# Connectors.net
KiCad netlist of a schematic drawn in Altium Designer
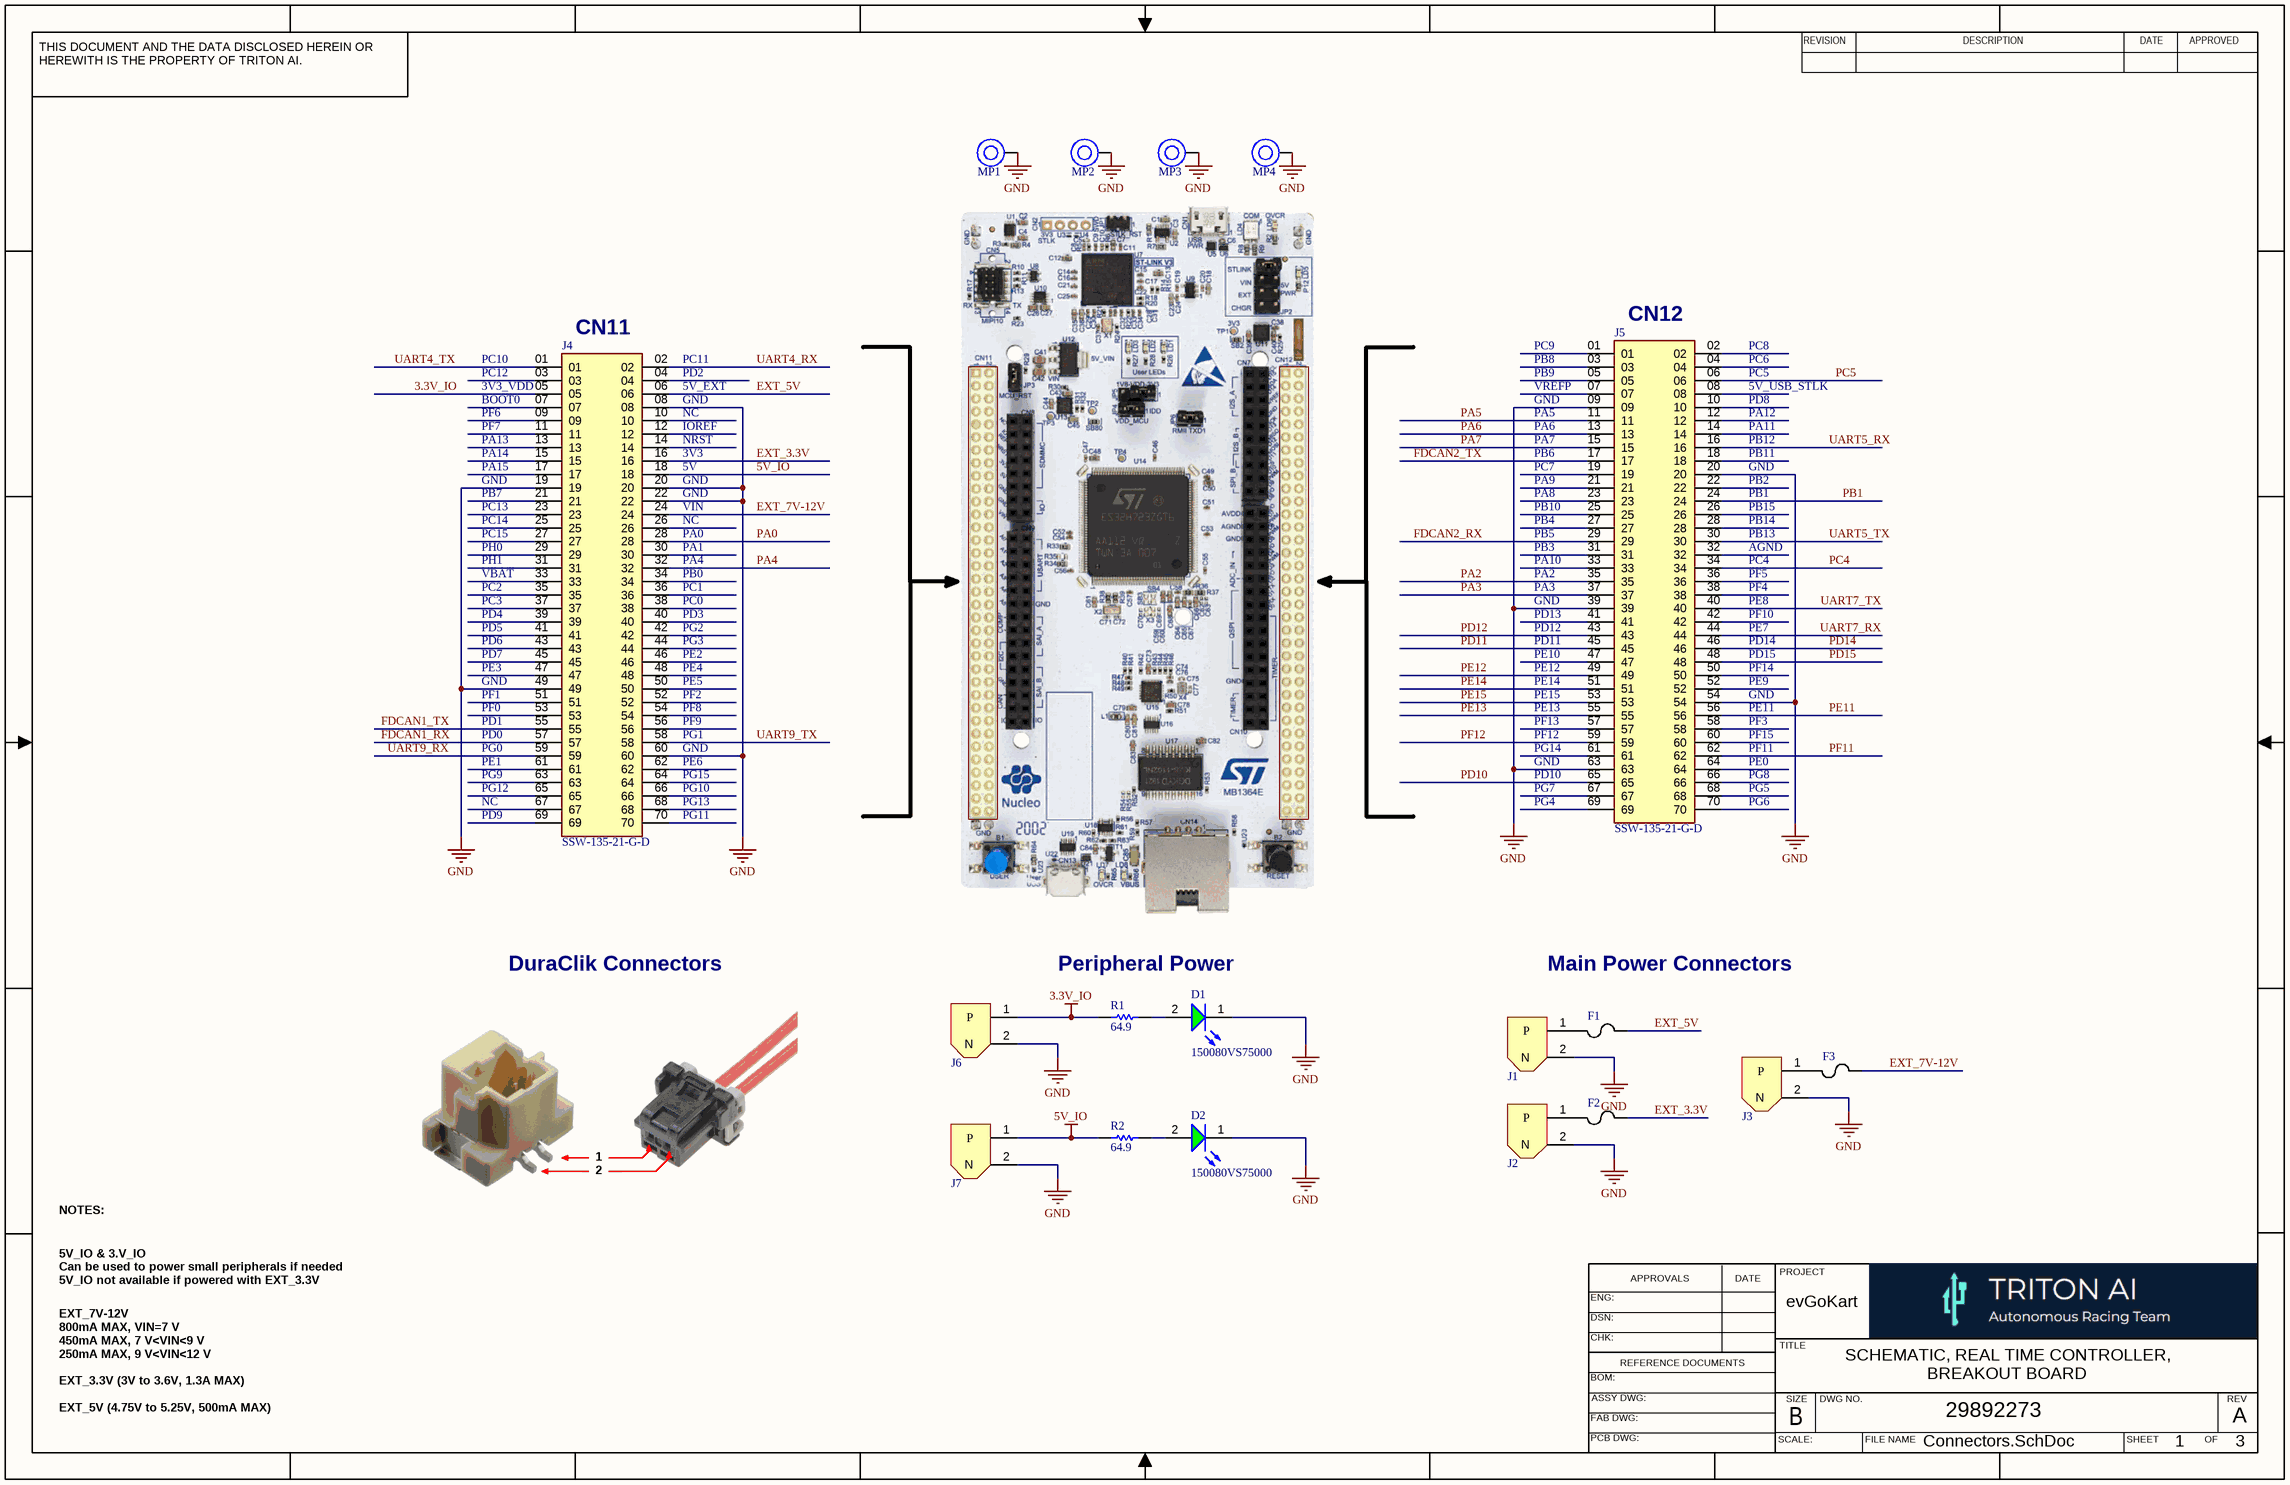
[diagram p0: Connectors.SchDoc]

(export (version "E")
  (design (tool "Eeschema 10.0.6"))
  (components
    (comp (ref "D1")
      (value "150080VS75000")
      (footprint "WL-SMCW_0805_150080xx75000")
      (description "WL-SMCW SMT Mono-Color Chip LED Waterclear")
      (libsource (lib "Altium Content Vault") (part "LED_Green_2A-1K"))
    )
    (comp (ref "D2")
      (value "150080VS75000")
      (footprint "WL-SMCW_0805_150080xx75000")
      (description "WL-SMCW SMT Mono-Color Chip LED Waterclear")
      (libsource (lib "Altium Content Vault") (part "LED_Green_2A-1K"))
    )
    (comp (ref "F1")
      (value "500mA")
      (footprint "FUS_VISHAY_MFU0805_VIS")
      (description "MFU0805FF00500P500")
      (libsource (lib "MFU0805FF00500P500") (part "MFU0805FF00500P500"))
    )
    (comp (ref "F2")
      (value "1.5A")
      (footprint "FUS_VISHAY_MFU0805_VIS")
      (description "MFU0805FF01500P100")
      (libsource (lib "MFU0805FF01500P100") (part "MFU0805FF01500P100"))
    )
    (comp (ref "F3")
      (value "800mA")
      (footprint "FUS_VISHAY_MFU0805_VIS")
      (description "MFU0805FF00800P100")
      (libsource (lib "MFU0805FF00800P100") (part "MFU0805FF00800P100"))
    )
    (comp (ref "J1")
      (value "XT30UPB-M")
      (footprint "XT30UPB-M")
      (description "Socket; DC supply; XT30; male; PIN: 2; on PCBs; THT; yellow; 15A; 500V")
      (fields (field (name "MF") "amass"))
      (libsource (lib "XT30UPB-M") (part "XT30UPB-M"))
    )
    (comp (ref "J2")
      (value "XT30UPB-M")
      (footprint "XT30UPB-M")
      (description "Socket; DC supply; XT30; male; PIN: 2; on PCBs; THT; yellow; 15A; 500V")
      (fields (field (name "MF") "amass"))
      (libsource (lib "XT30UPB-M") (part "XT30UPB-M"))
    )
    (comp (ref "J3")
      (value "XT30UPB-M")
      (footprint "XT30UPB-M")
      (description "Socket; DC supply; XT30; male; PIN: 2; on PCBs; THT; yellow; 15A; 500V")
      (fields (field (name "MF") "amass"))
      (libsource (lib "XT30UPB-M") (part "XT30UPB-M"))
    )
    (comp (ref "J4")
      (value "SSW-135-21-G-D")
      (footprint "SAMTEC_SSW-135-21-G-D")
      (fields (field (name "MF") "{'manufacturer': u'Samtec Inc.'}"))
      (libsource (lib "SSW-135-21-G-D") (part "SSW-135-21-G-D"))
    )
    (comp (ref "J5")
      (value "SSW-135-21-G-D")
      (footprint "SAMTEC_SSW-135-21-G-D")
      (fields (field (name "MF") "{'manufacturer': u'Samtec Inc.'}"))
      (libsource (lib "SSW-135-21-G-D") (part "SSW-135-21-G-D"))
    )
    (comp (ref "J6")
      (value "XT30UPB-M")
      (footprint "XT30UPB-M")
      (description "Socket; DC supply; XT30; male; PIN: 2; on PCBs; THT; yellow; 15A; 500V")
      (fields (field (name "MF") "amass"))
      (libsource (lib "XT30UPB-M") (part "XT30UPB-M"))
    )
    (comp (ref "J7")
      (value "XT30UPB-M")
      (footprint "XT30UPB-M")
      (description "Socket; DC supply; XT30; male; PIN: 2; on PCBs; THT; yellow; 15A; 500V")
      (fields (field (name "MF") "amass"))
      (libsource (lib "XT30UPB-M") (part "XT30UPB-M"))
    )
    (comp (ref "MP1")
      (value "M2.5 x 9mm")
      (footprint "9774090151")
      (description "WA-SMSI SMT Steel Spacer with internal Thread, OD 5.1mm, M2.5 x 9mm")
      (fields
        (field (name "MANUFACTURER PART NUMBER") "9774090151R")
        (field (name "MANUFACTURER") "Wurth Elektronik")
      )
      (libsource (lib "Altium_WA-SMSI_rev22a") (part "9774090151R"))
    )
    (comp (ref "MP2")
      (value "M2.5 x 9mm")
      (footprint "9774090151")
      (description "WA-SMSI SMT Steel Spacer with internal Thread, OD 5.1mm, M2.5 x 9mm")
      (fields
        (field (name "MANUFACTURER PART NUMBER") "9774090151R")
        (field (name "MANUFACTURER") "Wurth Elektronik")
      )
      (libsource (lib "Altium_WA-SMSI_rev22a") (part "9774090151R"))
    )
    (comp (ref "MP3")
      (value "M2.5 x 9mm")
      (footprint "9774090151")
      (description "WA-SMSI SMT Steel Spacer with internal Thread, OD 5.1mm, M2.5 x 9mm")
      (fields
        (field (name "MANUFACTURER PART NUMBER") "9774090151R")
        (field (name "MANUFACTURER") "Wurth Elektronik")
      )
      (libsource (lib "Altium_WA-SMSI_rev22a") (part "9774090151R"))
    )
    (comp (ref "MP4")
      (value "M2.5 x 9mm")
      (footprint "9774090151")
      (description "WA-SMSI SMT Steel Spacer with internal Thread, OD 5.1mm, M2.5 x 9mm")
      (fields
        (field (name "MANUFACTURER PART NUMBER") "9774090151R")
        (field (name "MANUFACTURER") "Wurth Elektronik")
      )
      (libsource (lib "Altium_WA-SMSI_rev22a") (part "9774090151R"))
    )
    (comp (ref "R1")
      (value "64.9")
      (footprint "RESC2013X60X35LL10T20")
      (fields (field (name "PART NUMBER") "RC0805FR-0764R9L") (field (name "MANUFACTURER") "Yageo"))
      (libsource (lib "Altium Content Vault") (part "RES"))
    )
    (comp (ref "R2")
      (value "64.9")
      (footprint "RESC2013X60X35LL10T20")
      (fields (field (name "PART NUMBER") "RC0805FR-0764R9L") (field (name "MANUFACTURER") "Yageo"))
      (libsource (lib "Altium Content Vault") (part "RES"))
    )
  )
  (nets
    (net (code "1") (name "/EXT_3.3V") (class "Default")
      (node (ref "F2") (pin "1") (pinfunction "1_1") (pintype "passive"))
      (node (ref "J4") (pin "16") (pinfunction "16_16") (pintype "passive"))
    )
    (net (code "2") (name "/EXT_5V") (class "Default")
      (node (ref "F1") (pin "1") (pinfunction "1_1") (pintype "passive"))
      (node (ref "J4") (pin "06") (pinfunction "06_06") (pintype "passive"))
    )
    (net (code "3") (name "/EXT_7V-12V") (class "Default")
      (node (ref "F3") (pin "1") (pinfunction "1_1") (pintype "passive"))
      (node (ref "J4") (pin "24") (pinfunction "24_24") (pintype "passive"))
    )
    (net (code "4") (name "/FDCAN1_RX") (class "Default")
      (node (ref "J4") (pin "57") (pinfunction "57_57") (pintype "passive"))
    )
    (net (code "5") (name "/FDCAN1_TX") (class "Default")
      (node (ref "J4") (pin "55") (pinfunction "55_55") (pintype "passive"))
    )
    (net (code "6") (name "/FDCAN2_RX") (class "Default")
      (node (ref "J5") (pin "29") (pinfunction "29_29") (pintype "passive"))
    )
    (net (code "7") (name "/FDCAN2_TX") (class "Default")
      (node (ref "J5") (pin "17") (pinfunction "17_17") (pintype "passive"))
    )
    (net (code "8") (name "/PA0") (class "Default")
      (node (ref "J4") (pin "28") (pinfunction "28_28") (pintype "passive"))
    )
    (net (code "9") (name "/PA2") (class "Default")
      (node (ref "J5") (pin "35") (pinfunction "35_35") (pintype "passive"))
    )
    (net (code "10") (name "/PA3") (class "Default")
      (node (ref "J5") (pin "37") (pinfunction "37_37") (pintype "passive"))
    )
    (net (code "11") (name "/PA4") (class "Default")
      (node (ref "J4") (pin "32") (pinfunction "32_32") (pintype "passive"))
    )
    (net (code "12") (name "/PA5") (class "Default")
      (node (ref "J5") (pin "11") (pinfunction "11_11") (pintype "passive"))
    )
    (net (code "13") (name "/PA6") (class "Default")
      (node (ref "J5") (pin "13") (pinfunction "13_13") (pintype "passive"))
    )
    (net (code "14") (name "/PA7") (class "Default")
      (node (ref "J5") (pin "15") (pinfunction "15_15") (pintype "passive"))
    )
    (net (code "15") (name "/PB1") (class "Default")
      (node (ref "J5") (pin "24") (pinfunction "24_24") (pintype "passive"))
    )
    (net (code "16") (name "/PC4") (class "Default")
      (node (ref "J5") (pin "34") (pinfunction "34_34") (pintype "passive"))
    )
    (net (code "17") (name "/PC5") (class "Default")
      (node (ref "J5") (pin "06") (pinfunction "06_06") (pintype "passive"))
    )
    (net (code "18") (name "/PD10") (class "Default")
      (node (ref "J5") (pin "65") (pinfunction "65_65") (pintype "passive"))
    )
    (net (code "19") (name "/PD11") (class "Default")
      (node (ref "J5") (pin "45") (pinfunction "45_45") (pintype "passive"))
    )
    (net (code "20") (name "/PD12") (class "Default")
      (node (ref "J5") (pin "43") (pinfunction "43_43") (pintype "passive"))
    )
    (net (code "21") (name "/PD14") (class "Default")
      (node (ref "J5") (pin "46") (pinfunction "46_46") (pintype "passive"))
    )
    (net (code "22") (name "/PD15") (class "Default")
      (node (ref "J5") (pin "48") (pinfunction "48_48") (pintype "passive"))
    )
    (net (code "23") (name "/PE11") (class "Default")
      (node (ref "J5") (pin "56") (pinfunction "56_56") (pintype "passive"))
    )
    (net (code "24") (name "/PE12") (class "Default")
      (node (ref "J5") (pin "49") (pinfunction "49_49") (pintype "passive"))
    )
    (net (code "25") (name "/PE13") (class "Default")
      (node (ref "J5") (pin "55") (pinfunction "55_55") (pintype "passive"))
    )
    (net (code "26") (name "/PE14") (class "Default")
      (node (ref "J5") (pin "51") (pinfunction "51_51") (pintype "passive"))
    )
    (net (code "27") (name "/PE15") (class "Default")
      (node (ref "J5") (pin "53") (pinfunction "53_53") (pintype "passive"))
    )
    (net (code "28") (name "/PF11") (class "Default")
      (node (ref "J5") (pin "62") (pinfunction "62_62") (pintype "passive"))
    )
    (net (code "29") (name "/PF12") (class "Default")
      (node (ref "J5") (pin "59") (pinfunction "59_59") (pintype "passive"))
    )
    (net (code "30") (name "/UART4_RX") (class "Default")
      (node (ref "J4") (pin "02") (pinfunction "02_02") (pintype "passive"))
    )
    (net (code "31") (name "/UART4_TX") (class "Default")
      (node (ref "J4") (pin "01") (pinfunction "01_01") (pintype "passive"))
    )
    (net (code "32") (name "/UART5_RX") (class "Default")
      (node (ref "J5") (pin "16") (pinfunction "16_16") (pintype "passive"))
    )
    (net (code "33") (name "/UART5_TX") (class "Default")
      (node (ref "J5") (pin "30") (pinfunction "30_30") (pintype "passive"))
    )
    (net (code "34") (name "/UART7_RX") (class "Default")
      (node (ref "J5") (pin "44") (pinfunction "44_44") (pintype "passive"))
    )
    (net (code "35") (name "/UART7_TX") (class "Default")
      (node (ref "J5") (pin "40") (pinfunction "40_40") (pintype "passive"))
    )
    (net (code "36") (name "/UART9_RX") (class "Default")
      (node (ref "J4") (pin "59") (pinfunction "59_59") (pintype "passive"))
    )
    (net (code "37") (name "/UART9_TX") (class "Default")
      (node (ref "J4") (pin "58") (pinfunction "58_58") (pintype "passive"))
    )
    (net (code "38") (name "3.3V_IO") (class "Default")
      (node (ref "J4") (pin "05") (pinfunction "05_05") (pintype "passive"))
      (node (ref "J6") (pin "1") (pinfunction "P_1") (pintype "passive"))
      (node (ref "R1") (pin "2") (pinfunction "2_2") (pintype "passive"))
    )
    (net (code "39") (name "5V_IO") (class "Default")
      (node (ref "J4") (pin "18") (pinfunction "18_18") (pintype "passive"))
      (node (ref "J7") (pin "1") (pinfunction "P_1") (pintype "passive"))
      (node (ref "R2") (pin "2") (pinfunction "2_2") (pintype "passive"))
    )
    (net (code "40") (name "GND") (class "Default")
      (node (ref "D1") (pin "1") (pinfunction "K_1") (pintype "passive"))
      (node (ref "D2") (pin "1") (pinfunction "K_1") (pintype "passive"))
      (node (ref "J1") (pin "2") (pinfunction "N_2") (pintype "passive"))
      (node (ref "J2") (pin "2") (pinfunction "N_2") (pintype "passive"))
      (node (ref "J3") (pin "2") (pinfunction "N_2") (pintype "passive"))
      (node (ref "J4") (pin "08") (pinfunction "08_08") (pintype "passive"))
      (node (ref "J4") (pin "19") (pinfunction "19_19") (pintype "passive"))
      (node (ref "J4") (pin "20") (pinfunction "20_20") (pintype "passive"))
      (node (ref "J4") (pin "22") (pinfunction "22_22") (pintype "passive"))
      (node (ref "J4") (pin "49") (pinfunction "49_49") (pintype "passive"))
      (node (ref "J4") (pin "60") (pinfunction "60_60") (pintype "passive"))
      (node (ref "J5") (pin "09") (pinfunction "09_09") (pintype "passive"))
      (node (ref "J5") (pin "20") (pinfunction "20_20") (pintype "passive"))
      (node (ref "J5") (pin "39") (pinfunction "39_39") (pintype "passive"))
      (node (ref "J5") (pin "54") (pinfunction "54_54") (pintype "passive"))
      (node (ref "J5") (pin "63") (pinfunction "63_63") (pintype "passive"))
      (node (ref "J6") (pin "2") (pinfunction "N_2") (pintype "passive"))
      (node (ref "J7") (pin "2") (pinfunction "N_2") (pintype "passive"))
      (node (ref "MP1") (pin "1") (pinfunction "1_1") (pintype "passive"))
      (node (ref "MP2") (pin "1") (pinfunction "1_1") (pintype "passive"))
      (node (ref "MP3") (pin "1") (pinfunction "1_1") (pintype "passive"))
      (node (ref "MP4") (pin "1") (pinfunction "1_1") (pintype "passive"))
    )
    (net (code "41") (name "Net-(D1-A)") (class "Default")
      (node (ref "D1") (pin "2") (pinfunction "A_2") (pintype "passive"))
      (node (ref "R1") (pin "1") (pinfunction "1_1") (pintype "passive"))
    )
    (net (code "42") (name "Net-(D2-A)") (class "Default")
      (node (ref "D2") (pin "2") (pinfunction "A_2") (pintype "passive"))
      (node (ref "R2") (pin "1") (pinfunction "1_1") (pintype "passive"))
    )
    (net (code "43") (name "Net-(J1-P)") (class "Default")
      (node (ref "F1") (pin "2") (pinfunction "2_2") (pintype "passive"))
      (node (ref "J1") (pin "1") (pinfunction "P_1") (pintype "passive"))
    )
    (net (code "44") (name "Net-(J2-P)") (class "Default")
      (node (ref "F2") (pin "2") (pinfunction "2_2") (pintype "passive"))
      (node (ref "J2") (pin "1") (pinfunction "P_1") (pintype "passive"))
    )
    (net (code "45") (name "Net-(J3-P)") (class "Default")
      (node (ref "F3") (pin "2") (pinfunction "2_2") (pintype "passive"))
      (node (ref "J3") (pin "1") (pinfunction "P_1") (pintype "passive"))
    )
    (net (code "46") (name "unconnected-(J4-Pad03)") (class "Default")
      (node (ref "J4") (pin "03") (pinfunction "03_03") (pintype "passive"))
    )
    (net (code "47") (name "unconnected-(J4-Pad04)") (class "Default")
      (node (ref "J4") (pin "04") (pinfunction "04_04") (pintype "passive"))
    )
    (net (code "48") (name "unconnected-(J4-Pad07)") (class "Default")
      (node (ref "J4") (pin "07") (pinfunction "07_07") (pintype "passive"))
    )
    (net (code "49") (name "unconnected-(J4-Pad09)") (class "Default")
      (node (ref "J4") (pin "09") (pinfunction "09_09") (pintype "passive"))
    )
    (net (code "50") (name "unconnected-(J4-Pad10)") (class "Default")
      (node (ref "J4") (pin "10") (pinfunction "10_10") (pintype "passive"))
    )
    (net (code "51") (name "unconnected-(J4-Pad11)") (class "Default")
      (node (ref "J4") (pin "11") (pinfunction "11_11") (pintype "passive"))
    )
    (net (code "52") (name "unconnected-(J4-Pad12)") (class "Default")
      (node (ref "J4") (pin "12") (pinfunction "12_12") (pintype "passive"))
    )
    (net (code "53") (name "unconnected-(J4-Pad13)") (class "Default")
      (node (ref "J4") (pin "13") (pinfunction "13_13") (pintype "passive"))
    )
    (net (code "54") (name "unconnected-(J4-Pad14)") (class "Default")
      (node (ref "J4") (pin "14") (pinfunction "14_14") (pintype "passive"))
    )
    (net (code "55") (name "unconnected-(J4-Pad15)") (class "Default")
      (node (ref "J4") (pin "15") (pinfunction "15_15") (pintype "passive"))
    )
    (net (code "56") (name "unconnected-(J4-Pad17)") (class "Default")
      (node (ref "J4") (pin "17") (pinfunction "17_17") (pintype "passive"))
    )
    (net (code "57") (name "unconnected-(J4-Pad21)") (class "Default")
      (node (ref "J4") (pin "21") (pinfunction "21_21") (pintype "passive"))
    )
    (net (code "58") (name "unconnected-(J4-Pad23)") (class "Default")
      (node (ref "J4") (pin "23") (pinfunction "23_23") (pintype "passive"))
    )
    (net (code "59") (name "unconnected-(J4-Pad25)") (class "Default")
      (node (ref "J4") (pin "25") (pinfunction "25_25") (pintype "passive"))
    )
    (net (code "60") (name "unconnected-(J4-Pad26)") (class "Default")
      (node (ref "J4") (pin "26") (pinfunction "26_26") (pintype "passive"))
    )
    (net (code "61") (name "unconnected-(J4-Pad27)") (class "Default")
      (node (ref "J4") (pin "27") (pinfunction "27_27") (pintype "passive"))
    )
    (net (code "62") (name "unconnected-(J4-Pad29)") (class "Default")
      (node (ref "J4") (pin "29") (pinfunction "29_29") (pintype "passive"))
    )
    (net (code "63") (name "unconnected-(J4-Pad30)") (class "Default")
      (node (ref "J4") (pin "30") (pinfunction "30_30") (pintype "passive"))
    )
    (net (code "64") (name "unconnected-(J4-Pad31)") (class "Default")
      (node (ref "J4") (pin "31") (pinfunction "31_31") (pintype "passive"))
    )
    (net (code "65") (name "unconnected-(J4-Pad33)") (class "Default")
      (node (ref "J4") (pin "33") (pinfunction "33_33") (pintype "passive"))
    )
    (net (code "66") (name "unconnected-(J4-Pad34)") (class "Default")
      (node (ref "J4") (pin "34") (pinfunction "34_34") (pintype "passive"))
    )
    (net (code "67") (name "unconnected-(J4-Pad35)") (class "Default")
      (node (ref "J4") (pin "35") (pinfunction "35_35") (pintype "passive"))
    )
    (net (code "68") (name "unconnected-(J4-Pad36)") (class "Default")
      (node (ref "J4") (pin "36") (pinfunction "36_36") (pintype "passive"))
    )
    (net (code "69") (name "unconnected-(J4-Pad37)") (class "Default")
      (node (ref "J4") (pin "37") (pinfunction "37_37") (pintype "passive"))
    )
    (net (code "70") (name "unconnected-(J4-Pad38)") (class "Default")
      (node (ref "J4") (pin "38") (pinfunction "38_38") (pintype "passive"))
    )
    (net (code "71") (name "unconnected-(J4-Pad39)") (class "Default")
      (node (ref "J4") (pin "39") (pinfunction "39_39") (pintype "passive"))
    )
    (net (code "72") (name "unconnected-(J4-Pad40)") (class "Default")
      (node (ref "J4") (pin "40") (pinfunction "40_40") (pintype "passive"))
    )
    (net (code "73") (name "unconnected-(J4-Pad41)") (class "Default")
      (node (ref "J4") (pin "41") (pinfunction "41_41") (pintype "passive"))
    )
    (net (code "74") (name "unconnected-(J4-Pad42)") (class "Default")
      (node (ref "J4") (pin "42") (pinfunction "42_42") (pintype "passive"))
    )
    (net (code "75") (name "unconnected-(J4-Pad43)") (class "Default")
      (node (ref "J4") (pin "43") (pinfunction "43_43") (pintype "passive"))
    )
    (net (code "76") (name "unconnected-(J4-Pad44)") (class "Default")
      (node (ref "J4") (pin "44") (pinfunction "44_44") (pintype "passive"))
    )
    (net (code "77") (name "unconnected-(J4-Pad45)") (class "Default")
      (node (ref "J4") (pin "45") (pinfunction "45_45") (pintype "passive"))
    )
    (net (code "78") (name "unconnected-(J4-Pad46)") (class "Default")
      (node (ref "J4") (pin "46") (pinfunction "46_46") (pintype "passive"))
    )
    (net (code "79") (name "unconnected-(J4-Pad47)") (class "Default")
      (node (ref "J4") (pin "47") (pinfunction "47_47") (pintype "passive"))
    )
    (net (code "80") (name "unconnected-(J4-Pad48)") (class "Default")
      (node (ref "J4") (pin "48") (pinfunction "48_48") (pintype "passive"))
    )
    (net (code "81") (name "unconnected-(J4-Pad50)") (class "Default")
      (node (ref "J4") (pin "50") (pinfunction "50_50") (pintype "passive"))
    )
    (net (code "82") (name "unconnected-(J4-Pad51)") (class "Default")
      (node (ref "J4") (pin "51") (pinfunction "51_51") (pintype "passive"))
    )
    (net (code "83") (name "unconnected-(J4-Pad52)") (class "Default")
      (node (ref "J4") (pin "52") (pinfunction "52_52") (pintype "passive"))
    )
    (net (code "84") (name "unconnected-(J4-Pad53)") (class "Default")
      (node (ref "J4") (pin "53") (pinfunction "53_53") (pintype "passive"))
    )
    (net (code "85") (name "unconnected-(J4-Pad54)") (class "Default")
      (node (ref "J4") (pin "54") (pinfunction "54_54") (pintype "passive"))
    )
    (net (code "86") (name "unconnected-(J4-Pad56)") (class "Default")
      (node (ref "J4") (pin "56") (pinfunction "56_56") (pintype "passive"))
    )
    (net (code "87") (name "unconnected-(J4-Pad61)") (class "Default")
      (node (ref "J4") (pin "61") (pinfunction "61_61") (pintype "passive"))
    )
    (net (code "88") (name "unconnected-(J4-Pad62)") (class "Default")
      (node (ref "J4") (pin "62") (pinfunction "62_62") (pintype "passive"))
    )
    (net (code "89") (name "unconnected-(J4-Pad63)") (class "Default")
      (node (ref "J4") (pin "63") (pinfunction "63_63") (pintype "passive"))
    )
    (net (code "90") (name "unconnected-(J4-Pad64)") (class "Default")
      (node (ref "J4") (pin "64") (pinfunction "64_64") (pintype "passive"))
    )
    (net (code "91") (name "unconnected-(J4-Pad65)") (class "Default")
      (node (ref "J4") (pin "65") (pinfunction "65_65") (pintype "passive"))
    )
    (net (code "92") (name "unconnected-(J4-Pad66)") (class "Default")
      (node (ref "J4") (pin "66") (pinfunction "66_66") (pintype "passive"))
    )
    (net (code "93") (name "unconnected-(J4-Pad67)") (class "Default")
      (node (ref "J4") (pin "67") (pinfunction "67_67") (pintype "passive"))
    )
    (net (code "94") (name "unconnected-(J4-Pad68)") (class "Default")
      (node (ref "J4") (pin "68") (pinfunction "68_68") (pintype "passive"))
    )
    (net (code "95") (name "unconnected-(J4-Pad69)") (class "Default")
      (node (ref "J4") (pin "69") (pinfunction "69_69") (pintype "passive"))
    )
    (net (code "96") (name "unconnected-(J4-Pad70)") (class "Default")
      (node (ref "J4") (pin "70") (pinfunction "70_70") (pintype "passive"))
    )
    (net (code "97") (name "unconnected-(J5-Pad01)") (class "Default")
      (node (ref "J5") (pin "01") (pinfunction "01_01") (pintype "passive"))
    )
    (net (code "98") (name "unconnected-(J5-Pad02)") (class "Default")
      (node (ref "J5") (pin "02") (pinfunction "02_02") (pintype "passive"))
    )
    (net (code "99") (name "unconnected-(J5-Pad03)") (class "Default")
      (node (ref "J5") (pin "03") (pinfunction "03_03") (pintype "passive"))
    )
    (net (code "100") (name "unconnected-(J5-Pad04)") (class "Default")
      (node (ref "J5") (pin "04") (pinfunction "04_04") (pintype "passive"))
    )
    (net (code "101") (name "unconnected-(J5-Pad05)") (class "Default")
      (node (ref "J5") (pin "05") (pinfunction "05_05") (pintype "passive"))
    )
    (net (code "102") (name "unconnected-(J5-Pad07)") (class "Default")
      (node (ref "J5") (pin "07") (pinfunction "07_07") (pintype "passive"))
    )
    (net (code "103") (name "unconnected-(J5-Pad08)") (class "Default")
      (node (ref "J5") (pin "08") (pinfunction "08_08") (pintype "passive"))
    )
    (net (code "104") (name "unconnected-(J5-Pad10)") (class "Default")
      (node (ref "J5") (pin "10") (pinfunction "10_10") (pintype "passive"))
    )
    (net (code "105") (name "unconnected-(J5-Pad12)") (class "Default")
      (node (ref "J5") (pin "12") (pinfunction "12_12") (pintype "passive"))
    )
    (net (code "106") (name "unconnected-(J5-Pad14)") (class "Default")
      (node (ref "J5") (pin "14") (pinfunction "14_14") (pintype "passive"))
    )
    (net (code "107") (name "unconnected-(J5-Pad18)") (class "Default")
      (node (ref "J5") (pin "18") (pinfunction "18_18") (pintype "passive"))
    )
    (net (code "108") (name "unconnected-(J5-Pad19)") (class "Default")
      (node (ref "J5") (pin "19") (pinfunction "19_19") (pintype "passive"))
    )
    (net (code "109") (name "unconnected-(J5-Pad21)") (class "Default")
      (node (ref "J5") (pin "21") (pinfunction "21_21") (pintype "passive"))
    )
    (net (code "110") (name "unconnected-(J5-Pad22)") (class "Default")
      (node (ref "J5") (pin "22") (pinfunction "22_22") (pintype "passive"))
    )
    (net (code "111") (name "unconnected-(J5-Pad23)") (class "Default")
      (node (ref "J5") (pin "23") (pinfunction "23_23") (pintype "passive"))
    )
    (net (code "112") (name "unconnected-(J5-Pad25)") (class "Default")
      (node (ref "J5") (pin "25") (pinfunction "25_25") (pintype "passive"))
    )
    (net (code "113") (name "unconnected-(J5-Pad26)") (class "Default")
      (node (ref "J5") (pin "26") (pinfunction "26_26") (pintype "passive"))
    )
    (net (code "114") (name "unconnected-(J5-Pad27)") (class "Default")
      (node (ref "J5") (pin "27") (pinfunction "27_27") (pintype "passive"))
    )
    (net (code "115") (name "unconnected-(J5-Pad28)") (class "Default")
      (node (ref "J5") (pin "28") (pinfunction "28_28") (pintype "passive"))
    )
    (net (code "116") (name "unconnected-(J5-Pad31)") (class "Default")
      (node (ref "J5") (pin "31") (pinfunction "31_31") (pintype "passive"))
    )
    (net (code "117") (name "unconnected-(J5-Pad32)") (class "Default")
      (node (ref "J5") (pin "32") (pinfunction "32_32") (pintype "passive"))
    )
    (net (code "118") (name "unconnected-(J5-Pad33)") (class "Default")
      (node (ref "J5") (pin "33") (pinfunction "33_33") (pintype "passive"))
    )
    (net (code "119") (name "unconnected-(J5-Pad36)") (class "Default")
      (node (ref "J5") (pin "36") (pinfunction "36_36") (pintype "passive"))
    )
    (net (code "120") (name "unconnected-(J5-Pad38)") (class "Default")
      (node (ref "J5") (pin "38") (pinfunction "38_38") (pintype "passive"))
    )
    (net (code "121") (name "unconnected-(J5-Pad41)") (class "Default")
      (node (ref "J5") (pin "41") (pinfunction "41_41") (pintype "passive"))
    )
    (net (code "122") (name "unconnected-(J5-Pad42)") (class "Default")
      (node (ref "J5") (pin "42") (pinfunction "42_42") (pintype "passive"))
    )
    (net (code "123") (name "unconnected-(J5-Pad47)") (class "Default")
      (node (ref "J5") (pin "47") (pinfunction "47_47") (pintype "passive"))
    )
    (net (code "124") (name "unconnected-(J5-Pad50)") (class "Default")
      (node (ref "J5") (pin "50") (pinfunction "50_50") (pintype "passive"))
    )
    (net (code "125") (name "unconnected-(J5-Pad52)") (class "Default")
      (node (ref "J5") (pin "52") (pinfunction "52_52") (pintype "passive"))
    )
    (net (code "126") (name "unconnected-(J5-Pad57)") (class "Default")
      (node (ref "J5") (pin "57") (pinfunction "57_57") (pintype "passive"))
    )
    (net (code "127") (name "unconnected-(J5-Pad58)") (class "Default")
      (node (ref "J5") (pin "58") (pinfunction "58_58") (pintype "passive"))
    )
    (net (code "128") (name "unconnected-(J5-Pad60)") (class "Default")
      (node (ref "J5") (pin "60") (pinfunction "60_60") (pintype "passive"))
    )
    (net (code "129") (name "unconnected-(J5-Pad61)") (class "Default")
      (node (ref "J5") (pin "61") (pinfunction "61_61") (pintype "passive"))
    )
    (net (code "130") (name "unconnected-(J5-Pad64)") (class "Default")
      (node (ref "J5") (pin "64") (pinfunction "64_64") (pintype "passive"))
    )
    (net (code "131") (name "unconnected-(J5-Pad66)") (class "Default")
      (node (ref "J5") (pin "66") (pinfunction "66_66") (pintype "passive"))
    )
    (net (code "132") (name "unconnected-(J5-Pad67)") (class "Default")
      (node (ref "J5") (pin "67") (pinfunction "67_67") (pintype "passive"))
    )
    (net (code "133") (name "unconnected-(J5-Pad68)") (class "Default")
      (node (ref "J5") (pin "68") (pinfunction "68_68") (pintype "passive"))
    )
    (net (code "134") (name "unconnected-(J5-Pad69)") (class "Default")
      (node (ref "J5") (pin "69") (pinfunction "69_69") (pintype "passive"))
    )
    (net (code "135") (name "unconnected-(J5-Pad70)") (class "Default")
      (node (ref "J5") (pin "70") (pinfunction "70_70") (pintype "passive"))
    )
  )
)
